# boombox_power_high_amp.net
KiCad netlist of a schematic drawn in EAGLE
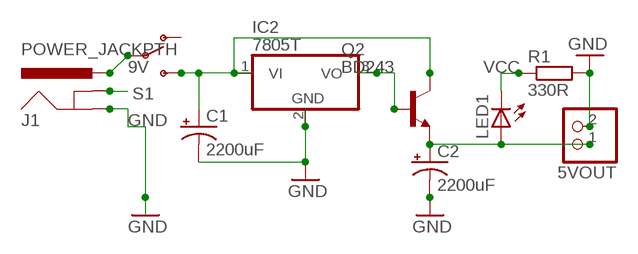
[diagram p0: schematic, sheet 1]

(export (version "E")
  (design (tool "Eeschema 10.0.6"))
  (components
    (comp (ref "5VOUT")
      (value "PINHD-1X2/90")
      (footprint "eagle-import:1X02_90")
      (libsource (lib "eagle-import") (part "PINHD-1X2/90"))
    )
    (comp (ref "C1")
      (value "2200uF")
      (footprint "eagle-import:CPOL-RADIAL-1000UF-25V")
      (libsource (lib "eagle-import") (part "CAP_POLPTH4"))
    )
    (comp (ref "C2")
      (value "2200uF")
      (footprint "eagle-import:CPOL-RADIAL-1000UF-25V")
      (libsource (lib "eagle-import") (part "CAP_POLPTH4"))
    )
    (comp (ref "IC2")
      (value "7805T")
      (footprint "eagle-import:TO220H")
      (libsource (lib "eagle-import") (part "78T05"))
    )
    (comp (ref "J1")
      (value "POWER_JACKPTH")
      (footprint "eagle-import:POWER_JACK_PTH")
      (libsource (lib "eagle-import") (part "POWER_JACKPTH"))
    )
    (comp (ref "LED1")
      (value "LED3MM")
      (footprint "eagle-import:LED3MM")
      (libsource (lib "eagle-import") (part "LED3MM"))
    )
    (comp (ref "Q2")
      (value "BD243")
      (footprint "eagle-import:TO220")
      (libsource (lib "eagle-import") (part "BD243"))
    )
    (comp (ref "R1")
      (value "330R")
      (footprint "eagle-import:0309V")
      (libsource (lib "eagle-import") (part "R-EU_0309/V"))
    )
    (comp (ref "S1")
      (value "SWITCH-SPSTPTH")
      (footprint "eagle-import:SWITCH-SPDT")
      (libsource (lib "eagle-import") (part "SWITCH-SPSTPTH"))
    )
  )
  (nets
    (net (code "1") (name "/9V") (class "Default")
      (node (ref "C1") (pin "1") (pinfunction "+_1") (pintype "passive"))
      (node (ref "IC2") (pin "1") (pinfunction "VI_1") (pintype "input"))
      (node (ref "Q2") (pin "2") (pinfunction "C_2") (pintype "passive"))
      (node (ref "S1") (pin "3") (pinfunction "S_3") (pintype "passive"))
    )
    (net (code "2") (name "/VCC") (class "Default")
      (node (ref "IC2") (pin "3") (pinfunction "VO_3") (pintype "passive"))
      (node (ref "Q2") (pin "1") (pinfunction "B_1") (pintype "passive"))
    )
    (net (code "3") (name "GND") (class "Default")
      (node (ref "5VOUT") (pin "2") (pinfunction "2_2") (pintype "passive"))
      (node (ref "C1") (pin "2") (pinfunction "-_2") (pintype "passive"))
      (node (ref "C2") (pin "2") (pinfunction "-_2") (pintype "passive"))
      (node (ref "IC2") (pin "2") (pinfunction "GND_2") (pintype "passive"))
      (node (ref "J1") (pin "GND") (pinfunction "GND_GND") (pintype "bidirectional"))
      (node (ref "R1") (pin "2") (pinfunction "2_2") (pintype "passive"))
    )
    (net (code "4") (name "Net-(C2-+)") (class "Default")
      (node (ref "5VOUT") (pin "1") (pinfunction "1_1") (pintype "passive"))
      (node (ref "C2") (pin "1") (pinfunction "+_1") (pintype "passive"))
      (node (ref "LED1") (pin "A") (pinfunction "A_A") (pintype "passive"))
      (node (ref "Q2") (pin "3") (pinfunction "E_3") (pintype "passive"))
    )
    (net (code "5") (name "Net-(LED1-C)") (class "Default")
      (node (ref "LED1") (pin "K") (pinfunction "C_K") (pintype "passive"))
      (node (ref "R1") (pin "1") (pinfunction "1_1") (pintype "passive"))
    )
    (net (code "6") (name "Net-(S1-P)") (class "Default")
      (node (ref "J1") (pin "PWR") (pinfunction "PWR_PWR") (pintype "bidirectional"))
      (node (ref "S1") (pin "2") (pinfunction "P_2") (pintype "passive"))
    )
    (net (code "7") (name "unconnected-(J1-PadGNDBREAK)") (class "Default")
      (node (ref "J1") (pin "GNDBREAK") (pinfunction "GNDBREAK_GNDBREAK") (pintype "bidirectional"))
    )
    (net (code "8") (name "unconnected-(S1-O-Pad1)") (class "Default")
      (node (ref "S1") (pin "1") (pinfunction "O_1") (pintype "passive"))
    )
  )
)
